# HOPE_RFID_V0_1.net
KiCad netlist of a schematic drawn in EAGLE
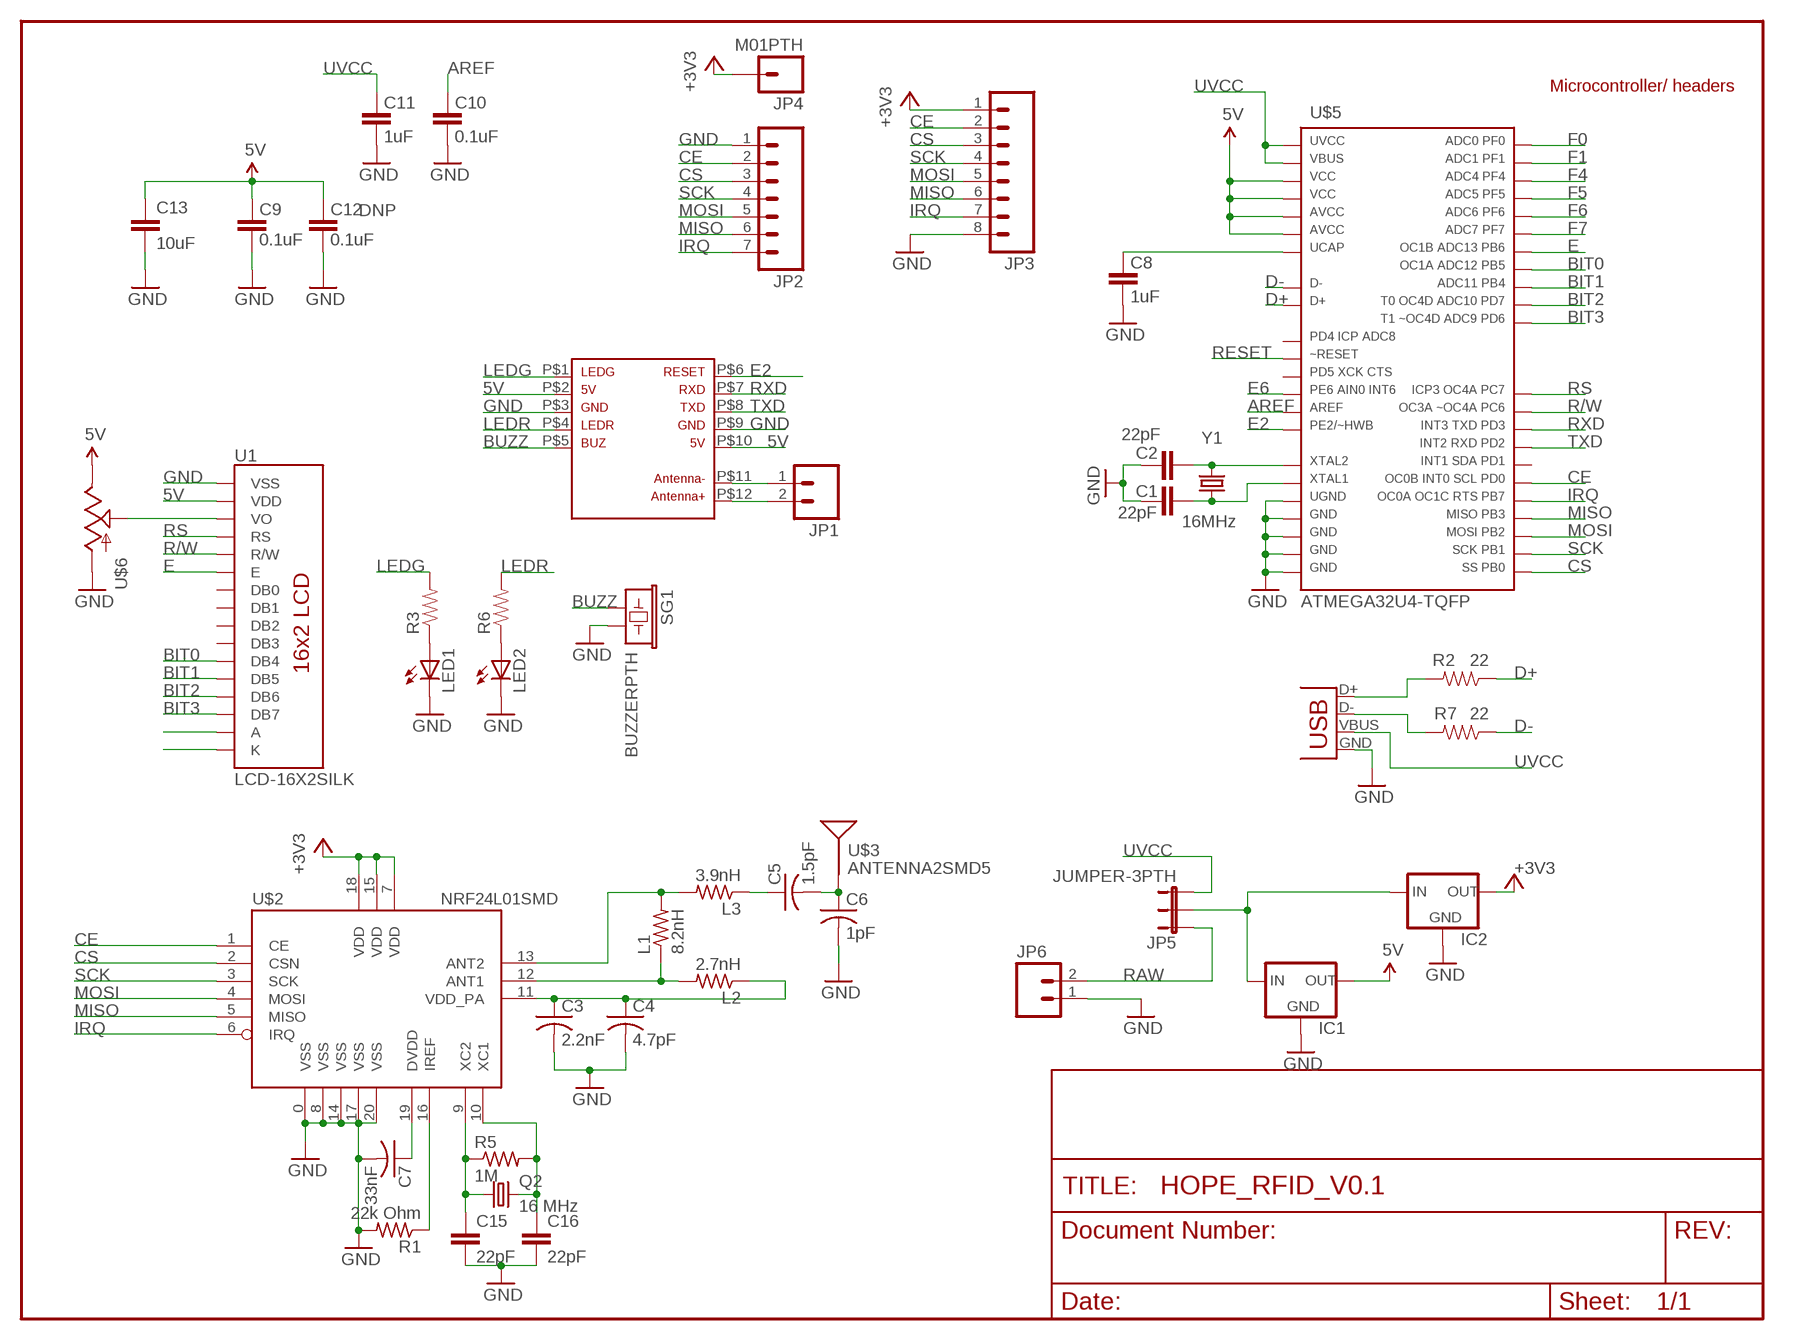
[diagram p0: schematic, sheet 1]

(export (version "E")
  (design (tool "Eeschema 10.0.6"))
  (components
    (comp (ref "C1")
      (value "22pF")
      (footprint "eagle-import:0805")
      (libsource (lib "eagle-import") (part "CAP0805"))
    )
    (comp (ref "C2")
      (value "22pF")
      (footprint "eagle-import:0805")
      (libsource (lib "eagle-import") (part "CAP0805"))
    )
    (comp (ref "C3")
      (value "2.2nF")
      (footprint "eagle-import:C0402")
      (libsource (lib "eagle-import") (part "C-USC0402"))
    )
    (comp (ref "C4")
      (value "4.7pF")
      (footprint "eagle-import:C0402")
      (libsource (lib "eagle-import") (part "C-USC0402"))
    )
    (comp (ref "C5")
      (value "1.5pF")
      (footprint "eagle-import:C0402")
      (libsource (lib "eagle-import") (part "C-USC0402"))
    )
    (comp (ref "C6")
      (value "1pF")
      (footprint "eagle-import:C0402")
      (libsource (lib "eagle-import") (part "C-USC0402"))
    )
    (comp (ref "C7")
      (value "33nF")
      (footprint "eagle-import:C0402")
      (libsource (lib "eagle-import") (part "C-USC0402"))
    )
    (comp (ref "C8")
      (value "1uF")
      (footprint "eagle-import:0603-CAP")
      (libsource (lib "eagle-import") (part "CAP0603-CAP"))
    )
    (comp (ref "C9")
      (value "0.1uF")
      (footprint "eagle-import:0603-CAP")
      (libsource (lib "eagle-import") (part "CAP0603-CAP"))
    )
    (comp (ref "C10")
      (value "0.1uF")
      (footprint "eagle-import:0603-CAP")
      (libsource (lib "eagle-import") (part "CAP0603-CAP"))
    )
    (comp (ref "C11")
      (value "1uF")
      (footprint "eagle-import:0603-CAP")
      (libsource (lib "eagle-import") (part "CAP0603-CAP"))
    )
    (comp (ref "C12")
      (value "0.1uF")
      (footprint "eagle-import:0603-CAP")
      (libsource (lib "eagle-import") (part "CAP0603-CAP"))
    )
    (comp (ref "C13")
      (value "10uF")
      (footprint "eagle-import:C2012")
      (libsource (lib "eagle-import") (part "C-EUC2012"))
    )
    (comp (ref "C15")
      (value "22pF")
      (footprint "eagle-import:0603-CAP")
      (libsource (lib "eagle-import") (part "CAP0603-CAP"))
    )
    (comp (ref "C16")
      (value "22pF")
      (footprint "eagle-import:0603-CAP")
      (libsource (lib "eagle-import") (part "CAP0603-CAP"))
    )
    (comp (ref "IC1")
      (value "V_REG_78XXSIDE")
      (footprint "eagle-import:78XXL")
      (libsource (lib "eagle-import") (part "V_REG_78XXSIDE"))
    )
    (comp (ref "IC2")
      (value "V_REG_78XXSIDE")
      (footprint "eagle-import:78XXL")
      (libsource (lib "eagle-import") (part "V_REG_78XXSIDE"))
    )
    (comp (ref "JP1")
      (value "M02PTH")
      (footprint "eagle-import:1X02")
      (libsource (lib "eagle-import") (part "M02PTH"))
    )
    (comp (ref "JP2")
      (value "M07")
      (footprint "eagle-import:1X07")
      (libsource (lib "eagle-import") (part "M07"))
    )
    (comp (ref "JP3")
      (value "M081X08")
      (footprint "eagle-import:1X08")
      (libsource (lib "eagle-import") (part "M081X08"))
    )
    (comp (ref "JP4")
      (value "M01PTH")
      (footprint "eagle-import:1X01")
      (libsource (lib "eagle-import") (part "M01PTH"))
    )
    (comp (ref "JP5")
      (value "JUMPER-3PTH")
      (footprint "eagle-import:1X03")
      (libsource (lib "eagle-import") (part "JUMPER-3PTH"))
    )
    (comp (ref "JP6")
      (value "M023.5MM")
      (footprint "eagle-import:SCREWTERMINAL-3.5MM-2")
      (libsource (lib "eagle-import") (part "M023.5MM"))
    )
    (comp (ref "L1")
      (value "8.2nH")
      (footprint "eagle-import:R0402")
      (libsource (lib "eagle-import") (part "R-US_R0402"))
    )
    (comp (ref "L2")
      (value "2.7nH")
      (footprint "eagle-import:R0402")
      (libsource (lib "eagle-import") (part "R-US_R0402"))
    )
    (comp (ref "L3")
      (value "3.9nH")
      (footprint "eagle-import:R0402")
      (libsource (lib "eagle-import") (part "R-US_R0402"))
    )
    (comp (ref "LED1")
      (value "LED5MM")
      (footprint "eagle-import:LED5MM")
      (libsource (lib "eagle-import") (part "LED5MM"))
    )
    (comp (ref "LED2")
      (value "LED5MM")
      (footprint "eagle-import:LED5MM")
      (libsource (lib "eagle-import") (part "LED5MM"))
    )
    (comp (ref "Q2")
      (value "16 MHz")
      (footprint "eagle-import:CRYSTAL-SMD-5X3")
      (libsource (lib "eagle-import") (part "SparkFun_CRYSTAL5X3"))
    )
    (comp (ref "R1")
      (value "22k Ohm")
      (footprint "eagle-import:R0805")
      (libsource (lib "eagle-import") (part "resistor_R-US_R0805"))
    )
    (comp (ref "R2")
      (value "22")
      (footprint "eagle-import:0805")
      (libsource (lib "eagle-import") (part "RESISTOR0805-RES"))
    )
    (comp (ref "R3")
      (value "RESISTORAXIAL-0.3")
      (footprint "eagle-import:AXIAL-0.3")
      (libsource (lib "eagle-import") (part "RESISTORAXIAL-0.3"))
    )
    (comp (ref "R5")
      (value "1M")
      (footprint "eagle-import:R0805")
      (libsource (lib "eagle-import") (part "resistor_R-US_R0805"))
    )
    (comp (ref "R6")
      (value "RESISTORAXIAL-0.3")
      (footprint "eagle-import:AXIAL-0.3")
      (libsource (lib "eagle-import") (part "RESISTORAXIAL-0.3"))
    )
    (comp (ref "R7")
      (value "22")
      (footprint "eagle-import:0805")
      (libsource (lib "eagle-import") (part "RESISTOR0805-RES"))
    )
    (comp (ref "SG1")
      (value "BUZZERPTH")
      (footprint "eagle-import:BUZZER-12MM")
      (libsource (lib "eagle-import") (part "BUZZERPTH"))
    )
    (comp (ref "U$1")
      (value "RDM880")
      (footprint "eagle-import:RDM880")
      (libsource (lib "eagle-import") (part "RDM880"))
    )
    (comp (ref "U$2")
      (value "NRF24L01SMD")
      (footprint "eagle-import:QFN20")
      (libsource (lib "eagle-import") (part "NRF24L01SMD"))
    )
    (comp (ref "U$3")
      (value "ANTENNA2SMD5")
      (footprint "eagle-import:ANTENNA-CHIP5")
      (libsource (lib "eagle-import") (part "ANTENNA2SMD5"))
    )
    (comp (ref "U$5")
      (value "ATMEGA32U4-TQFP")
      (footprint "eagle-import:TQFP44")
      (libsource (lib "eagle-import") (part "ATMEGA32U4-TQFP"))
    )
    (comp (ref "U$6")
      (value "POTTRIM")
      (footprint "eagle-import:TRIM_POT")
      (libsource (lib "eagle-import") (part "POTTRIM"))
    )
    (comp (ref "U1")
      (value "LCD-16X2SILK")
      (footprint "eagle-import:LCD-16X2")
      (libsource (lib "eagle-import") (part "LCD-16X2SILK"))
    )
    (comp (ref "X1")
      (value "USB")
      (footprint "eagle-import:USB-MINIB-NOHOLE")
      (libsource (lib "eagle-import") (part "USB"))
    )
    (comp (ref "Y1")
      (value "16MHz")
      (footprint "eagle-import:ABM2-8X4.5-CRYSTAL")
      (libsource (lib "eagle-import") (part "CRYSTAL"))
    )
  )
  (nets
    (net (code "1") (name "+3V3") (class "Default")
      (node (ref "IC2") (pin "OUT") (pinfunction "OUT_OUT") (pintype "output"))
      (node (ref "JP3") (pin "1") (pinfunction "1_1") (pintype "passive"))
      (node (ref "JP4") (pin "1") (pinfunction "1_1") (pintype "passive"))
      (node (ref "U$2") (pin "15") (pinfunction "VDD_15") (pintype "power_in"))
      (node (ref "U$2") (pin "18") (pinfunction "VDD_18") (pintype "power_in"))
      (node (ref "U$2") (pin "7") (pinfunction "VDD_7") (pintype "power_in"))
    )
    (net (code "2") (name "/AREF") (class "Default")
      (node (ref "C10") (pin "2") (pinfunction "2_2") (pintype "passive"))
      (node (ref "U$5") (pin "42") (pinfunction "P$42_42") (pintype "bidirectional"))
    )
    (net (code "3") (name "/BIT0") (class "Default")
      (node (ref "U$5") (pin "29") (pinfunction "P$29_29") (pintype "bidirectional"))
      (node (ref "U1") (pin "11") (pinfunction "DB4_11") (pintype "bidirectional"))
    )
    (net (code "4") (name "/BIT1") (class "Default")
      (node (ref "U$5") (pin "28") (pinfunction "P$28_28") (pintype "bidirectional"))
      (node (ref "U1") (pin "12") (pinfunction "DB5_12") (pintype "bidirectional"))
    )
    (net (code "5") (name "/BIT2") (class "Default")
      (node (ref "U$5") (pin "27") (pinfunction "P$27_27") (pintype "bidirectional"))
      (node (ref "U1") (pin "13") (pinfunction "DB6_13") (pintype "bidirectional"))
    )
    (net (code "6") (name "/BIT3") (class "Default")
      (node (ref "U$5") (pin "26") (pinfunction "P$26_26") (pintype "bidirectional"))
      (node (ref "U1") (pin "14") (pinfunction "DB7_14") (pintype "bidirectional"))
    )
    (net (code "7") (name "/BUZZ") (class "Default")
      (node (ref "SG1") (pin "+") (pinfunction "1_+") (pintype "passive"))
      (node (ref "U$1") (pin "P$5") (pinfunction "P$5_P$5") (pintype "bidirectional"))
    )
    (net (code "8") (name "/CE") (class "Default")
      (node (ref "JP2") (pin "2") (pinfunction "2_2") (pintype "passive"))
      (node (ref "JP3") (pin "2") (pinfunction "2_2") (pintype "passive"))
      (node (ref "U$2") (pin "1") (pinfunction "CE_1") (pintype "input"))
      (node (ref "U$5") (pin "18") (pinfunction "P$18_18") (pintype "bidirectional"))
    )
    (net (code "9") (name "/CS") (class "Default")
      (node (ref "JP2") (pin "3") (pinfunction "3_3") (pintype "passive"))
      (node (ref "JP3") (pin "3") (pinfunction "3_3") (pintype "passive"))
      (node (ref "U$2") (pin "2") (pinfunction "CSN_2") (pintype "input"))
      (node (ref "U$5") (pin "8") (pinfunction "P$8_8") (pintype "bidirectional"))
    )
    (net (code "10") (name "/D+") (class "Default")
      (node (ref "R2") (pin "1") (pinfunction "1_1") (pintype "passive"))
      (node (ref "U$5") (pin "4") (pinfunction "P$4_4") (pintype "bidirectional"))
    )
    (net (code "11") (name "/D-") (class "Default")
      (node (ref "R7") (pin "1") (pinfunction "1_1") (pintype "passive"))
      (node (ref "U$5") (pin "3") (pinfunction "P$3_3") (pintype "bidirectional"))
    )
    (net (code "12") (name "/E") (class "Default")
      (node (ref "U$5") (pin "30") (pinfunction "P$30_30") (pintype "bidirectional"))
      (node (ref "U1") (pin "6") (pinfunction "E_6") (pintype "input"))
    )
    (net (code "13") (name "/E2") (class "Default")
      (node (ref "U$1") (pin "P$6") (pinfunction "P$6_P$6") (pintype "bidirectional"))
      (node (ref "U$5") (pin "33") (pinfunction "P$33_33") (pintype "bidirectional"))
    )
    (net (code "14") (name "/E6") (class "Default")
      (node (ref "U$5") (pin "1") (pinfunction "P$1_1") (pintype "bidirectional"))
    )
    (net (code "15") (name "/F0") (class "Default")
      (node (ref "U$5") (pin "41") (pinfunction "P$41_41") (pintype "bidirectional"))
    )
    (net (code "16") (name "/F1") (class "Default")
      (node (ref "U$5") (pin "40") (pinfunction "P$40_40") (pintype "bidirectional"))
    )
    (net (code "17") (name "/F4") (class "Default")
      (node (ref "U$5") (pin "39") (pinfunction "P$39_39") (pintype "bidirectional"))
    )
    (net (code "18") (name "/F5") (class "Default")
      (node (ref "U$5") (pin "38") (pinfunction "P$38_38") (pintype "bidirectional"))
    )
    (net (code "19") (name "/F6") (class "Default")
      (node (ref "U$5") (pin "37") (pinfunction "P$37_37") (pintype "bidirectional"))
    )
    (net (code "20") (name "/F7") (class "Default")
      (node (ref "U$5") (pin "36") (pinfunction "P$36_36") (pintype "bidirectional"))
    )
    (net (code "21") (name "/IRQ") (class "Default")
      (node (ref "JP2") (pin "7") (pinfunction "7_7") (pintype "passive"))
      (node (ref "JP3") (pin "7") (pinfunction "7_7") (pintype "passive"))
      (node (ref "U$2") (pin "6") (pinfunction "IRQ_6") (pintype "output"))
      (node (ref "U$5") (pin "12") (pinfunction "P$12_12") (pintype "bidirectional"))
    )
    (net (code "22") (name "/LEDG") (class "Default")
      (node (ref "R3") (pin "P$2") (pinfunction "2_P$2") (pintype "passive"))
      (node (ref "U$1") (pin "P$1") (pinfunction "P$1_P$1") (pintype "bidirectional"))
    )
    (net (code "23") (name "/LEDR") (class "Default")
      (node (ref "R6") (pin "P$2") (pinfunction "2_P$2") (pintype "passive"))
      (node (ref "U$1") (pin "P$4") (pinfunction "P$4_P$4") (pintype "bidirectional"))
    )
    (net (code "24") (name "/MISO") (class "Default")
      (node (ref "JP2") (pin "6") (pinfunction "6_6") (pintype "passive"))
      (node (ref "JP3") (pin "6") (pinfunction "6_6") (pintype "passive"))
      (node (ref "U$2") (pin "5") (pinfunction "MISO_5") (pintype "output"))
      (node (ref "U$5") (pin "11") (pinfunction "P$11_11") (pintype "bidirectional"))
    )
    (net (code "25") (name "/MOSI") (class "Default")
      (node (ref "JP2") (pin "5") (pinfunction "5_5") (pintype "passive"))
      (node (ref "JP3") (pin "5") (pinfunction "5_5") (pintype "passive"))
      (node (ref "U$2") (pin "4") (pinfunction "MOSI_4") (pintype "input"))
      (node (ref "U$5") (pin "10") (pinfunction "P$10_10") (pintype "bidirectional"))
    )
    (net (code "26") (name "/RAW") (class "Default")
      (node (ref "JP5") (pin "1") (pinfunction "1_1") (pintype "passive"))
      (node (ref "JP6") (pin "2") (pinfunction "2_2") (pintype "passive"))
    )
    (net (code "27") (name "/RESET") (class "Default")
      (node (ref "U$5") (pin "13") (pinfunction "P$13_13") (pintype "bidirectional"))
    )
    (net (code "28") (name "/RS") (class "Default")
      (node (ref "U$5") (pin "32") (pinfunction "P$32_32") (pintype "bidirectional"))
      (node (ref "U1") (pin "4") (pinfunction "RS_4") (pintype "input"))
    )
    (net (code "29") (name "/RXD") (class "Default")
      (node (ref "U$1") (pin "P$7") (pinfunction "P$7_P$7") (pintype "bidirectional"))
      (node (ref "U$5") (pin "21") (pinfunction "P$21_21") (pintype "bidirectional"))
    )
    (net (code "30") (name "/R{slash}W") (class "Default")
      (node (ref "U$5") (pin "31") (pinfunction "P$31_31") (pintype "bidirectional"))
      (node (ref "U1") (pin "5") (pinfunction "R/W_5") (pintype "input"))
    )
    (net (code "31") (name "/SCK") (class "Default")
      (node (ref "JP2") (pin "4") (pinfunction "4_4") (pintype "passive"))
      (node (ref "JP3") (pin "4") (pinfunction "4_4") (pintype "passive"))
      (node (ref "U$2") (pin "3") (pinfunction "SCK_3") (pintype "input"))
      (node (ref "U$5") (pin "9") (pinfunction "P$9_9") (pintype "bidirectional"))
    )
    (net (code "32") (name "/TXD") (class "Default")
      (node (ref "U$1") (pin "P$8") (pinfunction "P$8_P$8") (pintype "bidirectional"))
      (node (ref "U$5") (pin "20") (pinfunction "P$20_20") (pintype "bidirectional"))
    )
    (net (code "33") (name "/UVCC") (class "Default")
      (node (ref "C11") (pin "2") (pinfunction "2_2") (pintype "passive"))
      (node (ref "JP5") (pin "3") (pinfunction "3_3") (pintype "passive"))
      (node (ref "U$5") (pin "2") (pinfunction "P$2_2") (pintype "bidirectional"))
      (node (ref "U$5") (pin "7") (pinfunction "P$7_7") (pintype "bidirectional"))
      (node (ref "X1") (pin "VBUS") (pinfunction "VBUS_VBUS") (pintype "bidirectional"))
    )
    (net (code "34") (name "5V") (class "Default")
      (node (ref "C12") (pin "2") (pinfunction "2_2") (pintype "passive"))
      (node (ref "C13") (pin "1") (pinfunction "1_1") (pintype "passive"))
      (node (ref "C9") (pin "2") (pinfunction "2_2") (pintype "passive"))
      (node (ref "IC1") (pin "OUT") (pinfunction "OUT_OUT") (pintype "output"))
      (node (ref "U$1") (pin "P$10") (pinfunction "P$10_P$10") (pintype "bidirectional"))
      (node (ref "U$1") (pin "P$2") (pinfunction "P$2_P$2") (pintype "bidirectional"))
      (node (ref "U$5") (pin "14") (pinfunction "P$14_14") (pintype "bidirectional"))
      (node (ref "U$5") (pin "24") (pinfunction "P$24_24") (pintype "bidirectional"))
      (node (ref "U$5") (pin "34") (pinfunction "P$34_34") (pintype "bidirectional"))
      (node (ref "U$5") (pin "44") (pinfunction "P$44_44") (pintype "bidirectional"))
      (node (ref "U$6") (pin "2") (pinfunction "E_2") (pintype "passive"))
      (node (ref "U1") (pin "2") (pinfunction "VDD_2") (pintype "power_in"))
    )
    (net (code "35") (name "GND") (class "Default")
      (node (ref "C1") (pin "2") (pinfunction "2_2") (pintype "passive"))
      (node (ref "C10") (pin "1") (pinfunction "1_1") (pintype "passive"))
      (node (ref "C11") (pin "1") (pinfunction "1_1") (pintype "passive"))
      (node (ref "C12") (pin "1") (pinfunction "1_1") (pintype "passive"))
      (node (ref "C13") (pin "2") (pinfunction "2_2") (pintype "passive"))
      (node (ref "C15") (pin "2") (pinfunction "2_2") (pintype "passive"))
      (node (ref "C16") (pin "2") (pinfunction "2_2") (pintype "passive"))
      (node (ref "C2") (pin "2") (pinfunction "2_2") (pintype "passive"))
      (node (ref "C3") (pin "2") (pinfunction "2_2") (pintype "passive"))
      (node (ref "C4") (pin "2") (pinfunction "2_2") (pintype "passive"))
      (node (ref "C6") (pin "2") (pinfunction "2_2") (pintype "passive"))
      (node (ref "C7") (pin "2") (pinfunction "2_2") (pintype "passive"))
      (node (ref "C8") (pin "1") (pinfunction "1_1") (pintype "passive"))
      (node (ref "C9") (pin "1") (pinfunction "1_1") (pintype "passive"))
      (node (ref "IC1") (pin "GND") (pinfunction "GND_GND") (pintype "input"))
      (node (ref "IC2") (pin "GND") (pinfunction "GND_GND") (pintype "input"))
      (node (ref "JP2") (pin "1") (pinfunction "1_1") (pintype "passive"))
      (node (ref "JP3") (pin "8") (pinfunction "8_8") (pintype "passive"))
      (node (ref "JP6") (pin "1") (pinfunction "1_1") (pintype "passive"))
      (node (ref "LED1") (pin "K") (pinfunction "C_K") (pintype "passive"))
      (node (ref "LED2") (pin "K") (pinfunction "C_K") (pintype "passive"))
      (node (ref "R1") (pin "2") (pinfunction "2_2") (pintype "passive"))
      (node (ref "SG1") (pin "-") (pinfunction "2_-") (pintype "passive"))
      (node (ref "U$1") (pin "P$3") (pinfunction "P$3_P$3") (pintype "bidirectional"))
      (node (ref "U$1") (pin "P$9") (pinfunction "P$9_P$9") (pintype "bidirectional"))
      (node (ref "U$2") (pin "0") (pinfunction "VSS_0") (pintype "power_in"))
      (node (ref "U$2") (pin "14") (pinfunction "VSS_14") (pintype "power_in"))
      (node (ref "U$2") (pin "17") (pinfunction "VSS_17") (pintype "power_in"))
      (node (ref "U$2") (pin "20") (pinfunction "VSS_20") (pintype "power_in"))
      (node (ref "U$2") (pin "8") (pinfunction "VSS_8") (pintype "power_in"))
      (node (ref "U$5") (pin "15") (pinfunction "P$15_15") (pintype "bidirectional"))
      (node (ref "U$5") (pin "23") (pinfunction "P$23_23") (pintype "bidirectional"))
      (node (ref "U$5") (pin "35") (pinfunction "P$35_35") (pintype "bidirectional"))
      (node (ref "U$5") (pin "43") (pinfunction "P$43_43") (pintype "bidirectional"))
      (node (ref "U$5") (pin "5") (pinfunction "P$5_5") (pintype "bidirectional"))
      (node (ref "U$6") (pin "3") (pinfunction "A_3") (pintype "passive"))
      (node (ref "U1") (pin "1") (pinfunction "VSS_1") (pintype "power_in"))
      (node (ref "X1") (pin "GND") (pinfunction "GND_GND") (pintype "bidirectional"))
    )
    (net (code "36") (name "Net-(C5-Pad1)") (class "Default")
      (node (ref "C5") (pin "1") (pinfunction "1_1") (pintype "passive"))
      (node (ref "L3") (pin "1") (pinfunction "1_1") (pintype "passive"))
    )
    (net (code "37") (name "Net-(IC1-PadIN)") (class "Default")
      (node (ref "IC1") (pin "IN") (pinfunction "IN_IN") (pintype "input"))
      (node (ref "IC2") (pin "IN") (pinfunction "IN_IN") (pintype "input"))
      (node (ref "JP5") (pin "2") (pinfunction "2_2") (pintype "passive"))
    )
    (net (code "38") (name "Net-(JP1-Pad1)") (class "Default")
      (node (ref "JP1") (pin "1") (pinfunction "1_1") (pintype "passive"))
      (node (ref "U$1") (pin "P$11") (pinfunction "P$11_P$11") (pintype "bidirectional"))
    )
    (net (code "39") (name "Net-(JP1-Pad2)") (class "Default")
      (node (ref "JP1") (pin "2") (pinfunction "2_2") (pintype "passive"))
      (node (ref "U$1") (pin "P$12") (pinfunction "P$12_P$12") (pintype "bidirectional"))
    )
    (net (code "40") (name "Net-(Q2-2)") (class "Default")
      (node (ref "C16") (pin "1") (pinfunction "1_1") (pintype "passive"))
      (node (ref "Q2") (pin "3") (pinfunction "2_3") (pintype "passive"))
      (node (ref "R5") (pin "2") (pinfunction "2_2") (pintype "passive"))
      (node (ref "U$2") (pin "10") (pinfunction "XC1_10") (pintype "input"))
    )
    (net (code "41") (name "Net-(R2-Pad2)") (class "Default")
      (node (ref "R2") (pin "2") (pinfunction "2_2") (pintype "passive"))
      (node (ref "X1") (pin "D+") (pinfunction "D+_D+") (pintype "bidirectional"))
    )
    (net (code "42") (name "Net-(R3-1)") (class "Default")
      (node (ref "LED1") (pin "A") (pinfunction "A_A") (pintype "passive"))
      (node (ref "R3") (pin "P$1") (pinfunction "1_P$1") (pintype "passive"))
    )
    (net (code "43") (name "Net-(R6-1)") (class "Default")
      (node (ref "LED2") (pin "A") (pinfunction "A_A") (pintype "passive"))
      (node (ref "R6") (pin "P$1") (pinfunction "1_P$1") (pintype "passive"))
    )
    (net (code "44") (name "Net-(R7-Pad2)") (class "Default")
      (node (ref "R7") (pin "2") (pinfunction "2_2") (pintype "passive"))
      (node (ref "X1") (pin "D-") (pinfunction "D-_D-") (pintype "bidirectional"))
    )
    (net (code "45") (name "Net-(U$2-ANT1)") (class "Default")
      (node (ref "L1") (pin "1") (pinfunction "1_1") (pintype "passive"))
      (node (ref "L2") (pin "2") (pinfunction "2_2") (pintype "passive"))
      (node (ref "U$2") (pin "12") (pinfunction "ANT1_12") (pintype "output"))
    )
    (net (code "46") (name "Net-(U$2-ANT2)") (class "Default")
      (node (ref "L1") (pin "2") (pinfunction "2_2") (pintype "passive"))
      (node (ref "L3") (pin "2") (pinfunction "2_2") (pintype "passive"))
      (node (ref "U$2") (pin "13") (pinfunction "ANT2_13") (pintype "output"))
    )
    (net (code "47") (name "Net-(U$2-DVDD)") (class "Default")
      (node (ref "C7") (pin "1") (pinfunction "1_1") (pintype "passive"))
      (node (ref "U$2") (pin "19") (pinfunction "DVDD_19") (pintype "power_in"))
    )
    (net (code "48") (name "Net-(U$2-IREF)") (class "Default")
      (node (ref "R1") (pin "1") (pinfunction "1_1") (pintype "passive"))
      (node (ref "U$2") (pin "16") (pinfunction "IREF_16") (pintype "input"))
    )
    (net (code "49") (name "Net-(U$2-VDD_PA)") (class "Default")
      (node (ref "C3") (pin "1") (pinfunction "1_1") (pintype "passive"))
      (node (ref "C4") (pin "1") (pinfunction "1_1") (pintype "passive"))
      (node (ref "L2") (pin "1") (pinfunction "1_1") (pintype "passive"))
      (node (ref "U$2") (pin "11") (pinfunction "VDD_PA_11") (pintype "power_in"))
    )
    (net (code "50") (name "Net-(U$2-XC2)") (class "Default")
      (node (ref "C15") (pin "1") (pinfunction "1_1") (pintype "passive"))
      (node (ref "Q2") (pin "1") (pinfunction "1_1") (pintype "passive"))
      (node (ref "R5") (pin "1") (pinfunction "1_1") (pintype "passive"))
      (node (ref "U$2") (pin "9") (pinfunction "XC2_9") (pintype "input"))
    )
    (net (code "51") (name "Net-(U$3-SIGNAL)") (class "Default")
      (node (ref "C5") (pin "2") (pinfunction "2_2") (pintype "passive"))
      (node (ref "C6") (pin "1") (pinfunction "1_1") (pintype "passive"))
      (node (ref "U$3") (pin "FEED") (pinfunction "SIGNAL_FEED") (pintype "bidirectional"))
    )
    (net (code "52") (name "Net-(U$5-P$6)") (class "Default")
      (node (ref "C8") (pin "2") (pinfunction "2_2") (pintype "passive"))
      (node (ref "U$5") (pin "6") (pinfunction "P$6_6") (pintype "bidirectional"))
    )
    (net (code "53") (name "Net-(U$5-P$16)") (class "Default")
      (node (ref "C1") (pin "1") (pinfunction "1_1") (pintype "passive"))
      (node (ref "U$5") (pin "16") (pinfunction "P$16_16") (pintype "bidirectional"))
      (node (ref "Y1") (pin "P$1") (pinfunction "1_P$1") (pintype "passive"))
    )
    (net (code "54") (name "Net-(U$5-P$17)") (class "Default")
      (node (ref "C2") (pin "1") (pinfunction "1_1") (pintype "passive"))
      (node (ref "U$5") (pin "17") (pinfunction "P$17_17") (pintype "bidirectional"))
      (node (ref "Y1") (pin "P$2") (pinfunction "2_P$2") (pintype "passive"))
    )
    (net (code "55") (name "Net-(U$6-S)") (class "Default")
      (node (ref "U$6") (pin "1") (pinfunction "S_1") (pintype "passive"))
      (node (ref "U1") (pin "3") (pinfunction "VO_3") (pintype "bidirectional"))
    )
    (net (code "56") (name "unconnected-(U$5-P$19-Pad19)") (class "Default")
      (node (ref "U$5") (pin "19") (pinfunction "P$19_19") (pintype "bidirectional"))
    )
    (net (code "57") (name "unconnected-(U$5-P$22-Pad22)") (class "Default")
      (node (ref "U$5") (pin "22") (pinfunction "P$22_22") (pintype "bidirectional"))
    )
    (net (code "58") (name "unconnected-(U$5-P$25-Pad25)") (class "Default")
      (node (ref "U$5") (pin "25") (pinfunction "P$25_25") (pintype "bidirectional"))
    )
    (net (code "59") (name "unconnected-(U1-A-Pad15)") (class "Default")
      (node (ref "U1") (pin "15") (pinfunction "A_15") (pintype "power_in"))
    )
    (net (code "60") (name "unconnected-(U1-DB0-Pad7)") (class "Default")
      (node (ref "U1") (pin "7") (pinfunction "DB0_7") (pintype "bidirectional"))
    )
    (net (code "61") (name "unconnected-(U1-DB1-Pad8)") (class "Default")
      (node (ref "U1") (pin "8") (pinfunction "DB1_8") (pintype "bidirectional"))
    )
    (net (code "62") (name "unconnected-(U1-DB2-Pad9)") (class "Default")
      (node (ref "U1") (pin "9") (pinfunction "DB2_9") (pintype "bidirectional"))
    )
    (net (code "63") (name "unconnected-(U1-DB3-Pad10)") (class "Default")
      (node (ref "U1") (pin "10") (pinfunction "DB3_10") (pintype "bidirectional"))
    )
    (net (code "64") (name "unconnected-(U1-K-Pad16)") (class "Default")
      (node (ref "U1") (pin "16") (pinfunction "K_16") (pintype "power_in"))
    )
  )
)
